# 2MosfetV1.net
KiCad netlist of a schematic drawn in EAGLE
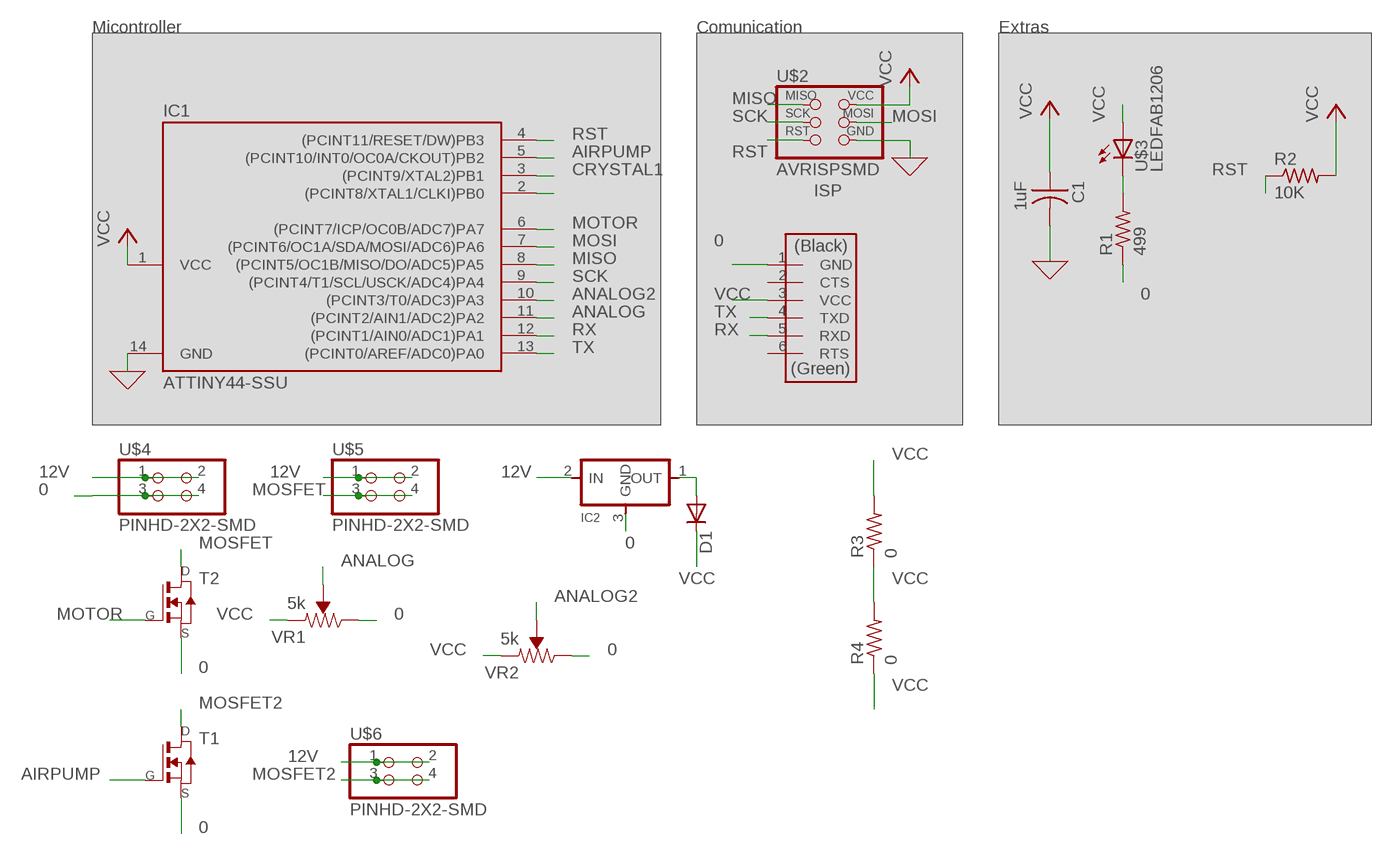
[diagram p0: schematic, sheet 1]

(export (version "E")
  (design (tool "Eeschema 10.0.6"))
  (components
    (comp (ref "C1")
      (value "1uF")
      (footprint "eagle-import:C1206FAB")
      (libsource (lib "eagle-import") (part "CAP-US1206FAB"))
    )
    (comp (ref "D1")
      (value "DIODESOD123")
      (footprint "eagle-import:SOD123")
      (libsource (lib "eagle-import") (part "DIODESOD123"))
    )
    (comp (ref "IC1")
      (value "ATTINY44-SSU")
      (footprint "eagle-import:SOIC14")
      (libsource (lib "eagle-import") (part "ATTINY44-SSU"))
    )
    (comp (ref "IC2")
      (value "REGULATORSOT23")
      (footprint "eagle-import:SOT23")
      (libsource (lib "eagle-import") (part "REGULATORSOT23"))
    )
    (comp (ref "R1")
      (value "499")
      (footprint "eagle-import:R1206FAB")
      (libsource (lib "eagle-import") (part "RES-US1206FAB"))
    )
    (comp (ref "R2")
      (value "10K")
      (footprint "eagle-import:R1206FAB")
      (libsource (lib "eagle-import") (part "RES-US1206FAB"))
    )
    (comp (ref "R3")
      (value "0")
      (footprint "eagle-import:R1206FAB")
      (libsource (lib "eagle-import") (part "RES-US1206FAB"))
    )
    (comp (ref "R4")
      (value "0")
      (footprint "eagle-import:R1206FAB")
      (libsource (lib "eagle-import") (part "RES-US1206FAB"))
    )
    (comp (ref "T1")
      (value "NMOSFETTO252")
      (footprint "eagle-import:TO252")
      (libsource (lib "eagle-import") (part "NMOSFETTO252"))
    )
    (comp (ref "T2")
      (value "NMOSFETTO252")
      (footprint "eagle-import:TO252")
      (libsource (lib "eagle-import") (part "NMOSFETTO252"))
    )
    (comp (ref "U$1")
      (value "FTDI-SMD-HEADER")
      (footprint "eagle-import:1X06SMD")
      (libsource (lib "eagle-import") (part "FTDI-SMD-HEADER"))
    )
    (comp (ref "U$2")
      (value "AVRISPSMD")
      (footprint "eagle-import:2X03SMD")
      (libsource (lib "eagle-import") (part "AVRISPSMD"))
    )
    (comp (ref "U$3")
      (value "LEDFAB1206")
      (footprint "eagle-import:LED1206FAB")
      (libsource (lib "eagle-import") (part "LEDFAB1206"))
    )
    (comp (ref "U$4")
      (value "PINHD-2X2-SMD")
      (footprint "eagle-import:2X02SMD")
      (libsource (lib "eagle-import") (part "PINHD-2X2-SMD"))
    )
    (comp (ref "U$5")
      (value "PINHD-2X2-SMD")
      (footprint "eagle-import:2X02SMD")
      (libsource (lib "eagle-import") (part "PINHD-2X2-SMD"))
    )
    (comp (ref "U$6")
      (value "PINHD-2X2-SMD")
      (footprint "eagle-import:2X02SMD")
      (libsource (lib "eagle-import") (part "PINHD-2X2-SMD"))
    )
    (comp (ref "VR1")
      (value "5k")
      (footprint "eagle-import:TRIMPOT-SMD-5MM")
      (libsource (lib "eagle-import") (part "TRIMPOT-SMD-5MM-CLOSED-1/4W-20%"))
    )
    (comp (ref "VR2")
      (value "5k")
      (footprint "eagle-import:TRIMPOT-SMD-5MM")
      (libsource (lib "eagle-import") (part "TRIMPOT-SMD-5MM-CLOSED-1/4W-20%"))
    )
  )
  (nets
    (net (code "1") (name "/12V") (class "Default")
      (node (ref "IC2") (pin "2") (pinfunction "IN_2") (pintype "bidirectional"))
      (node (ref "U$4") (pin "1") (pinfunction "1_1") (pintype "passive"))
      (node (ref "U$4") (pin "2") (pinfunction "2_2") (pintype "passive"))
      (node (ref "U$5") (pin "1") (pinfunction "1_1") (pintype "passive"))
      (node (ref "U$5") (pin "2") (pinfunction "2_2") (pintype "passive"))
      (node (ref "U$6") (pin "1") (pinfunction "1_1") (pintype "passive"))
      (node (ref "U$6") (pin "2") (pinfunction "2_2") (pintype "passive"))
    )
    (net (code "2") (name "/AIRPUMP") (class "Default")
      (node (ref "IC1") (pin "5") (pinfunction "(PCINT10/INT0/OC0A/CKOUT)PB2_5") (pintype "bidirectional"))
      (node (ref "T1") (pin "1") (pinfunction "G_1") (pintype "passive"))
    )
    (net (code "3") (name "/ANALOG") (class "Default")
      (node (ref "IC1") (pin "11") (pinfunction "(PCINT2/AIN1/ADC2)PA2_11") (pintype "bidirectional"))
      (node (ref "VR1") (pin "B") (pinfunction "WIPER_B") (pintype "passive"))
    )
    (net (code "4") (name "/ANALOG2") (class "Default")
      (node (ref "IC1") (pin "10") (pinfunction "(PCINT3/T0/ADC3)PA3_10") (pintype "bidirectional"))
      (node (ref "VR2") (pin "B") (pinfunction "WIPER_B") (pintype "passive"))
    )
    (net (code "5") (name "/CRYSTAL1") (class "Default")
      (node (ref "IC1") (pin "3") (pinfunction "(PCINT9/XTAL2)PB1_3") (pintype "bidirectional"))
    )
    (net (code "6") (name "/MISO") (class "Default")
      (node (ref "IC1") (pin "8") (pinfunction "(PCINT5/OC1B/MISO/DO/ADC5)PA5_8") (pintype "bidirectional"))
      (node (ref "U$2") (pin "1") (pinfunction "MISO_1") (pintype "passive"))
    )
    (net (code "7") (name "/MOSFET") (class "Default")
      (node (ref "T2") (pin "3") (pinfunction "D_3") (pintype "passive"))
      (node (ref "U$5") (pin "3") (pinfunction "3_3") (pintype "passive"))
      (node (ref "U$5") (pin "4") (pinfunction "4_4") (pintype "passive"))
    )
    (net (code "8") (name "/MOSFET2") (class "Default")
      (node (ref "T1") (pin "3") (pinfunction "D_3") (pintype "passive"))
      (node (ref "U$6") (pin "3") (pinfunction "3_3") (pintype "passive"))
      (node (ref "U$6") (pin "4") (pinfunction "4_4") (pintype "passive"))
    )
    (net (code "9") (name "/MOSI") (class "Default")
      (node (ref "IC1") (pin "7") (pinfunction "(PCINT6/OC1A/SDA/MOSI/ADC6)PA6_7") (pintype "bidirectional"))
      (node (ref "U$2") (pin "4") (pinfunction "MOSI_4") (pintype "passive"))
    )
    (net (code "10") (name "/MOTOR") (class "Default")
      (node (ref "IC1") (pin "6") (pinfunction "(PCINT7/ICP/OC0B/ADC7)PA7_6") (pintype "bidirectional"))
      (node (ref "T2") (pin "1") (pinfunction "G_1") (pintype "passive"))
    )
    (net (code "11") (name "/RST") (class "Default")
      (node (ref "IC1") (pin "4") (pinfunction "(PCINT11/RESET/DW)PB3_4") (pintype "bidirectional"))
      (node (ref "R2") (pin "1") (pinfunction "1_1") (pintype "passive"))
      (node (ref "U$2") (pin "5") (pinfunction "RST_5") (pintype "passive"))
    )
    (net (code "12") (name "/RX") (class "Default")
      (node (ref "IC1") (pin "12") (pinfunction "(PCINT1/AIN0/ADC1)PA1_12") (pintype "bidirectional"))
      (node (ref "U$1") (pin "5") (pinfunction "RXD_5") (pintype "bidirectional"))
    )
    (net (code "13") (name "/SCK") (class "Default")
      (node (ref "IC1") (pin "9") (pinfunction "(PCINT4/T1/SCL/USCK/ADC4)PA4_9") (pintype "bidirectional"))
      (node (ref "U$2") (pin "3") (pinfunction "SCK_3") (pintype "passive"))
    )
    (net (code "14") (name "/TX") (class "Default")
      (node (ref "IC1") (pin "13") (pinfunction "(PCINT0/AREF/ADC0)PA0_13") (pintype "bidirectional"))
      (node (ref "U$1") (pin "4") (pinfunction "TXD_4") (pintype "bidirectional"))
    )
    (net (code "15") (name "GND") (class "Default")
      (node (ref "C1") (pin "2") (pinfunction "2_2") (pintype "passive"))
      (node (ref "IC1") (pin "14") (pinfunction "GND_14") (pintype "power_in"))
      (node (ref "IC2") (pin "3") (pinfunction "GND_3") (pintype "bidirectional"))
      (node (ref "R1") (pin "1") (pinfunction "1_1") (pintype "passive"))
      (node (ref "T1") (pin "2") (pinfunction "S_2") (pintype "passive"))
      (node (ref "T2") (pin "2") (pinfunction "S_2") (pintype "passive"))
      (node (ref "U$1") (pin "1") (pinfunction "GND_1") (pintype "bidirectional"))
      (node (ref "U$2") (pin "6") (pinfunction "GND_6") (pintype "passive"))
      (node (ref "U$4") (pin "3") (pinfunction "3_3") (pintype "passive"))
      (node (ref "U$4") (pin "4") (pinfunction "4_4") (pintype "passive"))
      (node (ref "VR1") (pin "C") (pinfunction "CW_C") (pintype "passive"))
      (node (ref "VR2") (pin "C") (pinfunction "CW_C") (pintype "passive"))
    )
    (net (code "16") (name "Net-(D1-A)") (class "Default")
      (node (ref "D1") (pin "ANODE") (pinfunction "A_ANODE") (pintype "passive"))
      (node (ref "IC2") (pin "1") (pinfunction "OUT_1") (pintype "bidirectional"))
    )
    (net (code "17") (name "Net-(U$3-C)") (class "Default")
      (node (ref "R1") (pin "2") (pinfunction "2_2") (pintype "passive"))
      (node (ref "U$3") (pin "2") (pinfunction "C_2") (pintype "passive"))
    )
    (net (code "18") (name "VCC") (class "Default")
      (node (ref "C1") (pin "1") (pinfunction "1_1") (pintype "passive"))
      (node (ref "D1") (pin "CATHODE") (pinfunction "C_CATHODE") (pintype "passive"))
      (node (ref "IC1") (pin "1") (pinfunction "VCC_1") (pintype "power_in"))
      (node (ref "R2") (pin "2") (pinfunction "2_2") (pintype "passive"))
      (node (ref "R3") (pin "1") (pinfunction "1_1") (pintype "passive"))
      (node (ref "R3") (pin "2") (pinfunction "2_2") (pintype "passive"))
      (node (ref "R4") (pin "1") (pinfunction "1_1") (pintype "passive"))
      (node (ref "R4") (pin "2") (pinfunction "2_2") (pintype "passive"))
      (node (ref "U$1") (pin "3") (pinfunction "VCC_3") (pintype "bidirectional"))
      (node (ref "U$2") (pin "2") (pinfunction "VCC_2") (pintype "passive"))
      (node (ref "U$3") (pin "1") (pinfunction "A_1") (pintype "passive"))
      (node (ref "VR1") (pin "A") (pinfunction "CCW_A") (pintype "passive"))
      (node (ref "VR2") (pin "A") (pinfunction "CCW_A") (pintype "passive"))
    )
    (net (code "19") (name "unconnected-(IC1-(PCINT8{slash}XTAL1{slash}CLKI)PB0-Pad2)") (class "Default")
      (node (ref "IC1") (pin "2") (pinfunction "(PCINT8/XTAL1/CLKI)PB0_2") (pintype "bidirectional"))
    )
    (net (code "20") (name "unconnected-(U$1-CTS-Pad2)") (class "Default")
      (node (ref "U$1") (pin "2") (pinfunction "CTS_2") (pintype "bidirectional"))
    )
    (net (code "21") (name "unconnected-(U$1-RTS-Pad6)") (class "Default")
      (node (ref "U$1") (pin "6") (pinfunction "RTS_6") (pintype "bidirectional"))
    )
  )
)
